# Ref_Supply_Unit.net
KiCad netlist of a schematic drawn in Altium Designer
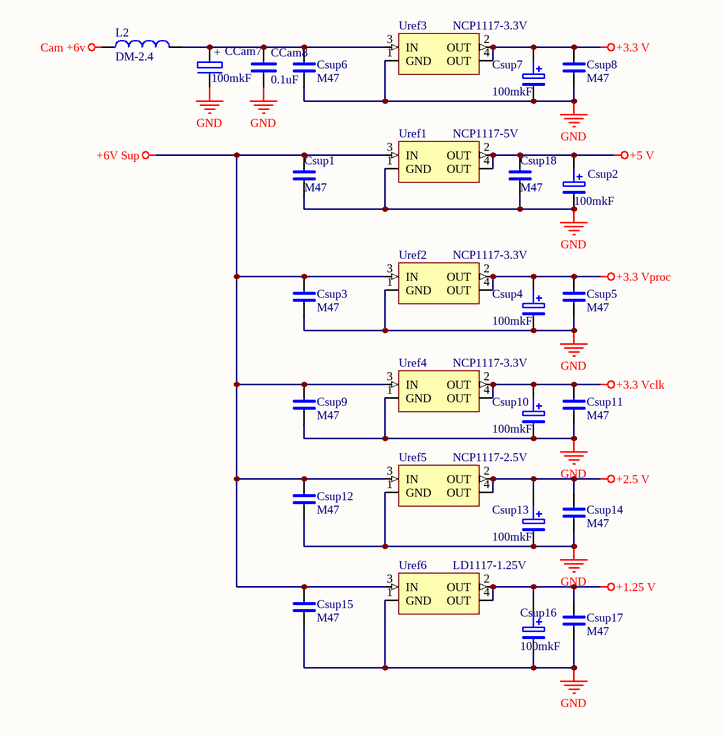
[diagram p0: Ref&Supply Unit.SchDoc]

(export (version "E")
  (design (tool "Eeschema 10.0.6"))
  (components
    (comp (ref "CCam7") (value "100mkF") (footprint "CEL-SMD300") (libsource (lib "vDevice") (part "C POL")))
    (comp (ref "CCam8") (value "0.1uF") (footprint "chip0805") (libsource (lib "vDevice") (part "C")))
    (comp (ref "Csup1") (value "M47") (footprint "chip0805") (libsource (lib "*") (part "C")))
    (comp (ref "Csup2") (value "100mkF") (footprint "CEL-SMD300") (libsource (lib "*") (part "C POL")))
    (comp (ref "Csup3") (value "M47") (footprint "chip0805") (libsource (lib "*") (part "C")))
    (comp (ref "Csup4") (value "100mkF") (footprint "CEL-SMD300") (libsource (lib "*") (part "C POL")))
    (comp (ref "Csup5") (value "M47") (footprint "chip0805") (libsource (lib "*") (part "C")))
    (comp (ref "Csup6") (value "M47") (footprint "chip0805") (libsource (lib "*") (part "C")))
    (comp (ref "Csup7") (value "100mkF") (footprint "CEL-SMD300") (libsource (lib "*") (part "C POL")))
    (comp (ref "Csup8") (value "M47") (footprint "chip0805") (libsource (lib "*") (part "C")))
    (comp (ref "Csup9") (value "M47") (footprint "chip0805") (libsource (lib "*") (part "C")))
    (comp (ref "Csup10") (value "100mkF") (footprint "CEL-SMD300") (libsource (lib "*") (part "C POL")))
    (comp (ref "Csup11") (value "M47") (footprint "chip0805") (libsource (lib "*") (part "C")))
    (comp (ref "Csup12") (value "M47") (footprint "chip0805") (libsource (lib "*") (part "C")))
    (comp (ref "Csup13") (value "100mkF") (footprint "CEL-SMD300") (libsource (lib "*") (part "C POL")))
    (comp (ref "Csup14") (value "M47") (footprint "chip0805") (libsource (lib "*") (part "C")))
    (comp (ref "Csup15") (value "M47") (footprint "chip0805") (libsource (lib "*") (part "C")))
    (comp (ref "Csup16") (value "100mkF") (footprint "CEL-SMD300") (libsource (lib "*") (part "C POL")))
    (comp (ref "Csup17") (value "M47") (footprint "chip0805") (libsource (lib "*") (part "C")))
    (comp (ref "Csup18") (value "M47") (footprint "chip0805") (libsource (lib "*") (part "C")))
    (comp (ref "L2") (value "DM-2.4") (footprint "DM-2.4") (libsource (lib "*") (part "INDUCTOR")))
    (comp (ref "Uref1")
      (value "NCP1117-5V")
      (footprint "SOT-223")
      (libsource (lib "vAnalog") (part "NCP1117-3.3V"))
    )
    (comp (ref "Uref2")
      (value "NCP1117-3.3V")
      (footprint "r_Package:TO-252")
      (libsource (lib "vAnalog") (part "NCP1117-3.3V"))
    )
    (comp (ref "Uref3")
      (value "NCP1117-3.3V")
      (footprint "r_Package:TO-252")
      (libsource (lib "vAnalog") (part "NCP1117-3.3V"))
    )
    (comp (ref "Uref4")
      (value "NCP1117-3.3V")
      (footprint "r_Package:TO-252")
      (libsource (lib "vAnalog") (part "NCP1117-3.3V"))
    )
    (comp (ref "Uref5")
      (value "NCP1117-2.5V")
      (footprint "TO-252")
      (libsource (lib "vAnalog") (part "NCP1117-3.3V"))
    )
    (comp (ref "Uref6")
      (value "LD1117-1.25V")
      (footprint "TO-252")
      (libsource (lib "vAnalog") (part "NCP1117-3.3V"))
    )
  )
  (nets
    (net (code "1") (name "+1.25 V") (class "Default")
      (node (ref "Csup16") (pin "+") (pinfunction "+_+") (pintype "passive"))
      (node (ref "Csup17") (pin "1") (pinfunction "1_1") (pintype "passive"))
      (node (ref "Uref6") (pin "2") (pinfunction "OUT_2") (pintype "output"))
      (node (ref "Uref6") (pin "4") (pinfunction "OUT_4") (pintype "passive"))
    )
    (net (code "2") (name "+2.5 V") (class "Default")
      (node (ref "Csup13") (pin "+") (pinfunction "+_+") (pintype "passive"))
      (node (ref "Csup14") (pin "1") (pinfunction "1_1") (pintype "passive"))
      (node (ref "Uref5") (pin "2") (pinfunction "OUT_2") (pintype "output"))
      (node (ref "Uref5") (pin "4") (pinfunction "OUT_4") (pintype "passive"))
    )
    (net (code "3") (name "+3.3 V") (class "Default")
      (node (ref "Csup7") (pin "+") (pinfunction "+_+") (pintype "passive"))
      (node (ref "Csup8") (pin "1") (pinfunction "1_1") (pintype "passive"))
      (node (ref "Uref3") (pin "2") (pinfunction "OUT_2") (pintype "output"))
      (node (ref "Uref3") (pin "4") (pinfunction "OUT_4") (pintype "passive"))
    )
    (net (code "4") (name "+3.3 Vclk") (class "Default")
      (node (ref "Csup10") (pin "+") (pinfunction "+_+") (pintype "passive"))
      (node (ref "Csup11") (pin "1") (pinfunction "1_1") (pintype "passive"))
      (node (ref "Uref4") (pin "2") (pinfunction "OUT_2") (pintype "output"))
      (node (ref "Uref4") (pin "4") (pinfunction "OUT_4") (pintype "passive"))
    )
    (net (code "5") (name "+3.3 Vproc") (class "Default")
      (node (ref "Csup4") (pin "+") (pinfunction "+_+") (pintype "passive"))
      (node (ref "Csup5") (pin "1") (pinfunction "1_1") (pintype "passive"))
      (node (ref "Uref2") (pin "2") (pinfunction "OUT_2") (pintype "output"))
      (node (ref "Uref2") (pin "4") (pinfunction "OUT_4") (pintype "passive"))
    )
    (net (code "6") (name "+5 V") (class "Default")
      (node (ref "Csup18") (pin "1") (pinfunction "1_1") (pintype "passive"))
      (node (ref "Csup2") (pin "+") (pinfunction "+_+") (pintype "passive"))
      (node (ref "Uref1") (pin "2") (pinfunction "OUT_2") (pintype "output"))
      (node (ref "Uref1") (pin "4") (pinfunction "OUT_4") (pintype "passive"))
    )
    (net (code "7") (name "+6V Sup") (class "Default")
      (node (ref "Csup1") (pin "1") (pinfunction "1_1") (pintype "passive"))
      (node (ref "Csup12") (pin "1") (pinfunction "1_1") (pintype "passive"))
      (node (ref "Csup15") (pin "1") (pinfunction "1_1") (pintype "passive"))
      (node (ref "Csup3") (pin "1") (pinfunction "1_1") (pintype "passive"))
      (node (ref "Csup9") (pin "1") (pinfunction "1_1") (pintype "passive"))
      (node (ref "Uref1") (pin "3") (pinfunction "IN_3") (pintype "input"))
      (node (ref "Uref2") (pin "3") (pinfunction "IN_3") (pintype "input"))
      (node (ref "Uref4") (pin "3") (pinfunction "IN_3") (pintype "input"))
      (node (ref "Uref5") (pin "3") (pinfunction "IN_3") (pintype "input"))
      (node (ref "Uref6") (pin "3") (pinfunction "IN_3") (pintype "input"))
    )
    (net (code "8") (name "Cam +6v") (class "Default")
      (node (ref "L2") (pin "1") (pinfunction "1_1") (pintype "passive"))
    )
    (net (code "9") (name "GND") (class "Default")
      (node (ref "CCam7") (pin "-") (pinfunction "-_-") (pintype "passive"))
      (node (ref "CCam8") (pin "2") (pinfunction "2_2") (pintype "passive"))
      (node (ref "Csup1") (pin "2") (pinfunction "2_2") (pintype "passive"))
      (node (ref "Csup10") (pin "-") (pinfunction "-_-") (pintype "passive"))
      (node (ref "Csup11") (pin "2") (pinfunction "2_2") (pintype "passive"))
      (node (ref "Csup12") (pin "2") (pinfunction "2_2") (pintype "passive"))
      (node (ref "Csup13") (pin "-") (pinfunction "-_-") (pintype "passive"))
      (node (ref "Csup14") (pin "2") (pinfunction "2_2") (pintype "passive"))
      (node (ref "Csup15") (pin "2") (pinfunction "2_2") (pintype "passive"))
      (node (ref "Csup16") (pin "-") (pinfunction "-_-") (pintype "passive"))
      (node (ref "Csup17") (pin "2") (pinfunction "2_2") (pintype "passive"))
      (node (ref "Csup18") (pin "2") (pinfunction "2_2") (pintype "passive"))
      (node (ref "Csup2") (pin "-") (pinfunction "-_-") (pintype "passive"))
      (node (ref "Csup3") (pin "2") (pinfunction "2_2") (pintype "passive"))
      (node (ref "Csup4") (pin "-") (pinfunction "-_-") (pintype "passive"))
      (node (ref "Csup5") (pin "2") (pinfunction "2_2") (pintype "passive"))
      (node (ref "Csup6") (pin "2") (pinfunction "2_2") (pintype "passive"))
      (node (ref "Csup7") (pin "-") (pinfunction "-_-") (pintype "passive"))
      (node (ref "Csup8") (pin "2") (pinfunction "2_2") (pintype "passive"))
      (node (ref "Csup9") (pin "2") (pinfunction "2_2") (pintype "passive"))
      (node (ref "Uref1") (pin "1") (pinfunction "GND_1") (pintype "power_in"))
      (node (ref "Uref2") (pin "1") (pinfunction "GND_1") (pintype "power_in"))
      (node (ref "Uref3") (pin "1") (pinfunction "GND_1") (pintype "power_in"))
      (node (ref "Uref4") (pin "1") (pinfunction "GND_1") (pintype "power_in"))
      (node (ref "Uref5") (pin "1") (pinfunction "GND_1") (pintype "power_in"))
      (node (ref "Uref6") (pin "1") (pinfunction "GND_1") (pintype "power_in"))
    )
    (net (code "10") (name "Net-(Uref3-IN)") (class "Default")
      (node (ref "CCam7") (pin "+") (pinfunction "+_+") (pintype "passive"))
      (node (ref "CCam8") (pin "1") (pinfunction "1_1") (pintype "passive"))
      (node (ref "Csup6") (pin "1") (pinfunction "1_1") (pintype "passive"))
      (node (ref "L2") (pin "2") (pinfunction "2_2") (pintype "passive"))
      (node (ref "Uref3") (pin "3") (pinfunction "IN_3") (pintype "input"))
    )
  )
)
